# Rev_3.net
KiCad netlist of a schematic drawn in EAGLE
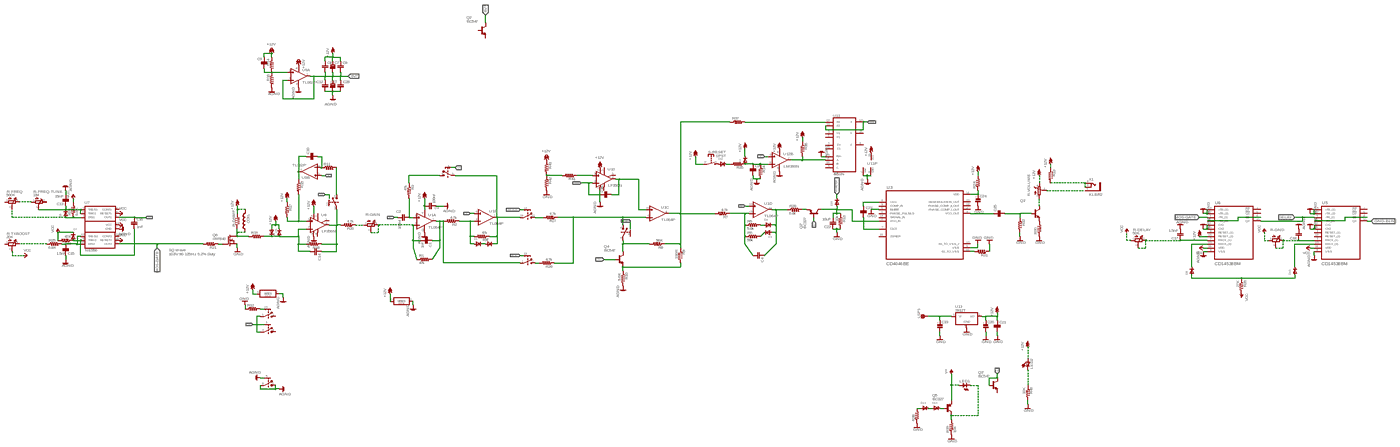
[diagram p0: schematic, sheet 1, overview]
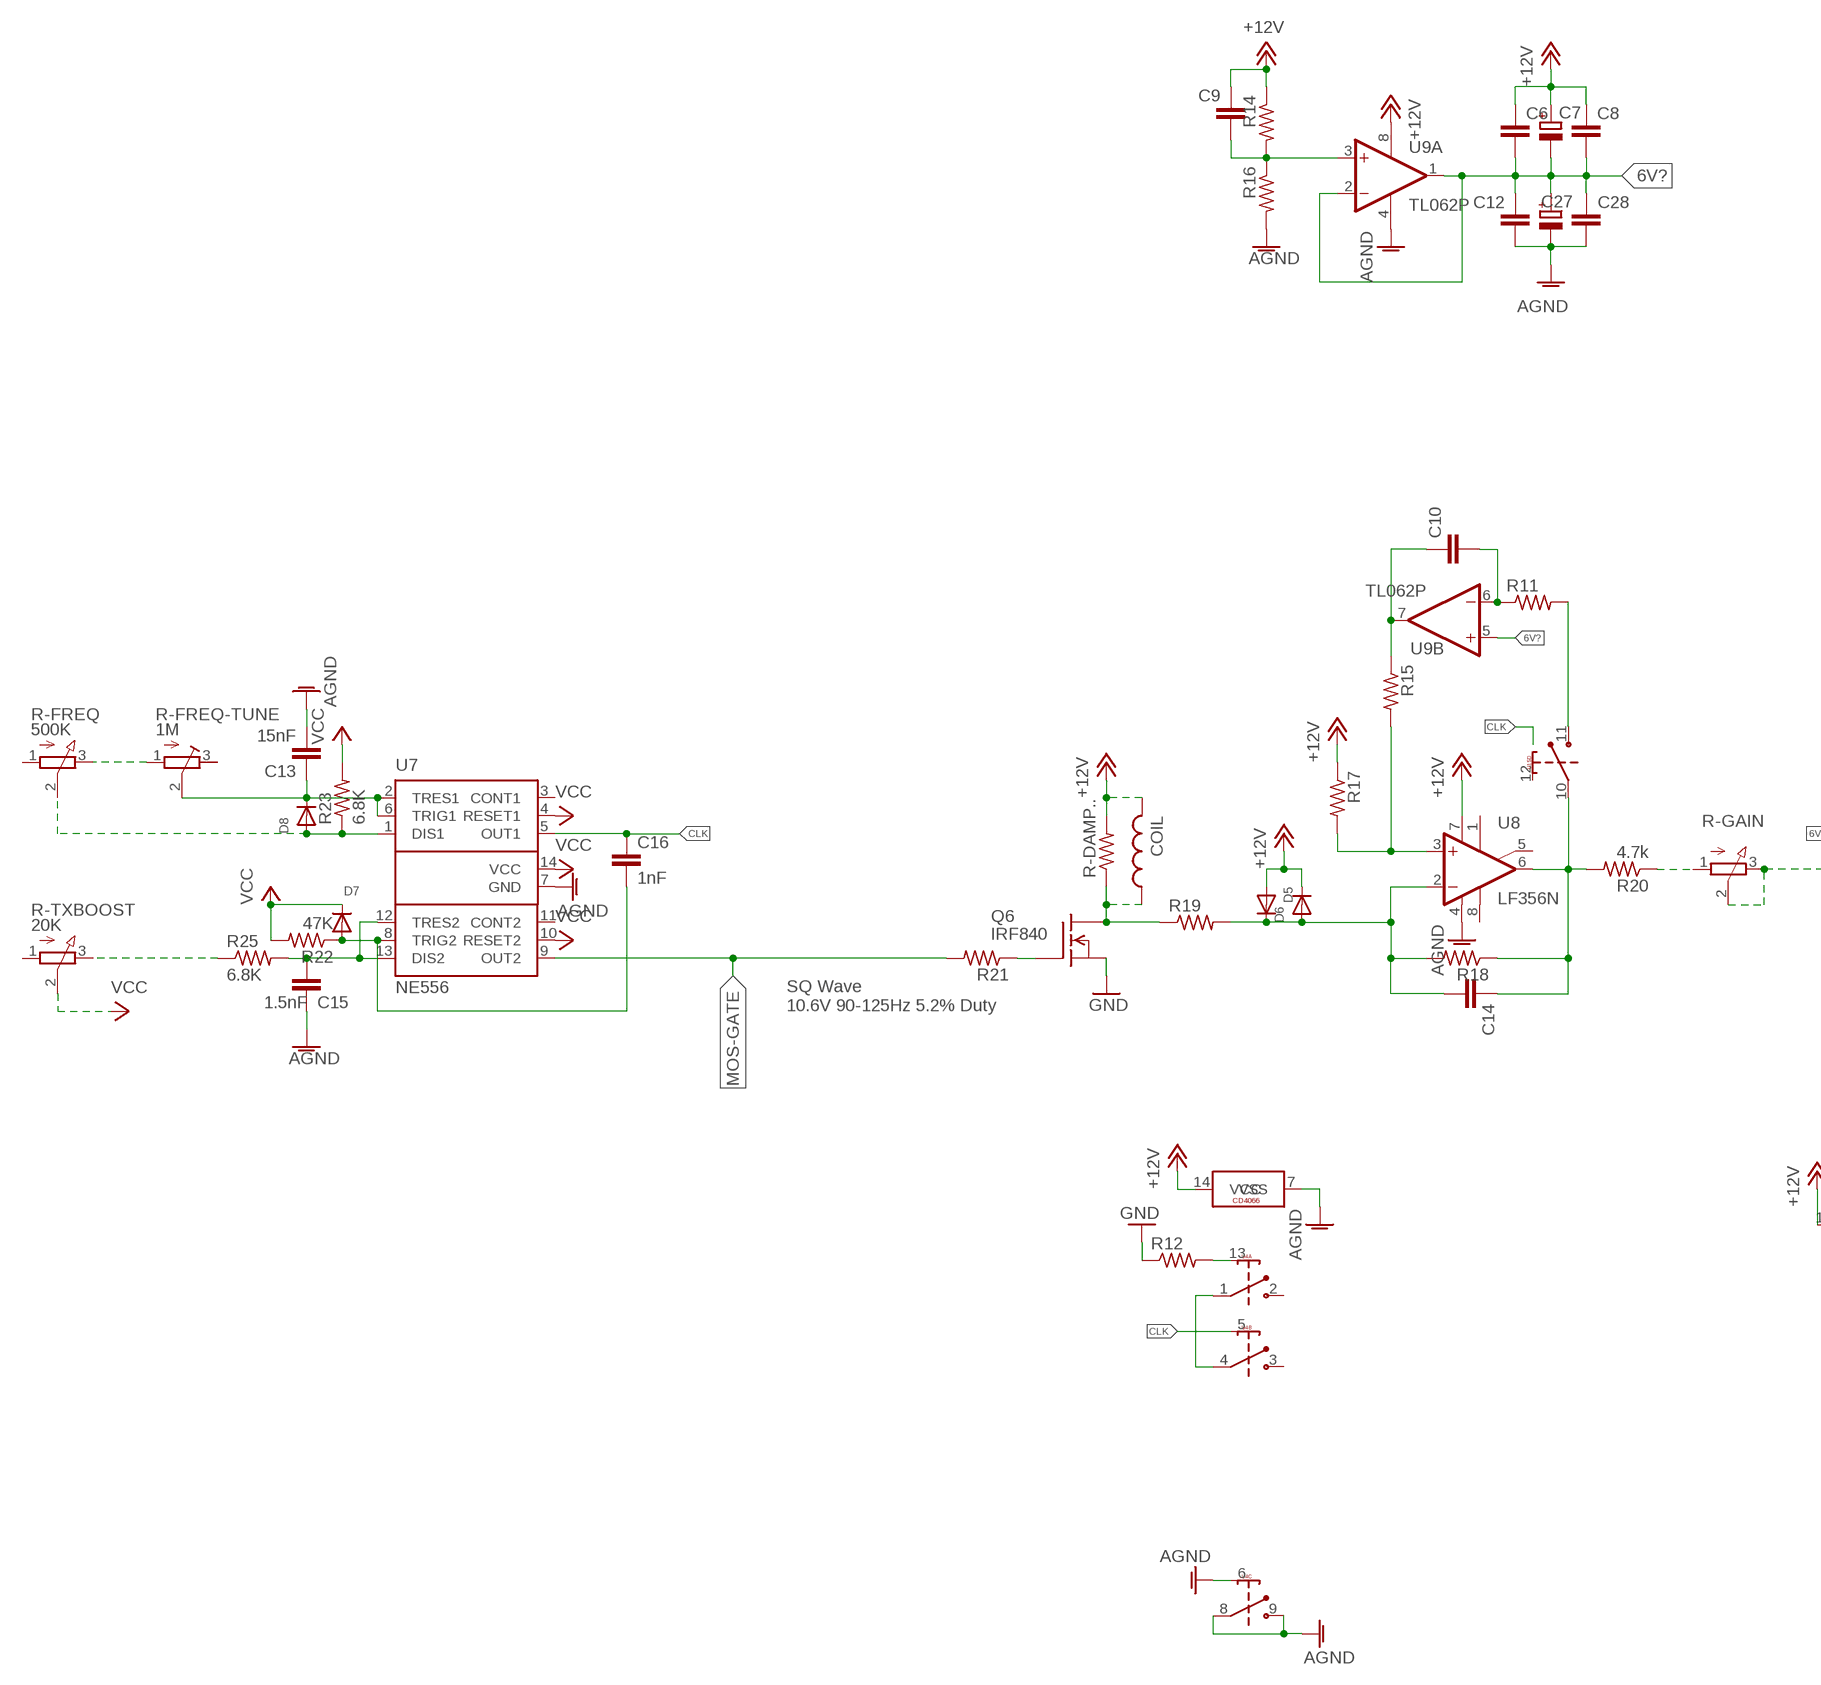
[diagram p1: schematic, sheet 1, part 1 of 4]
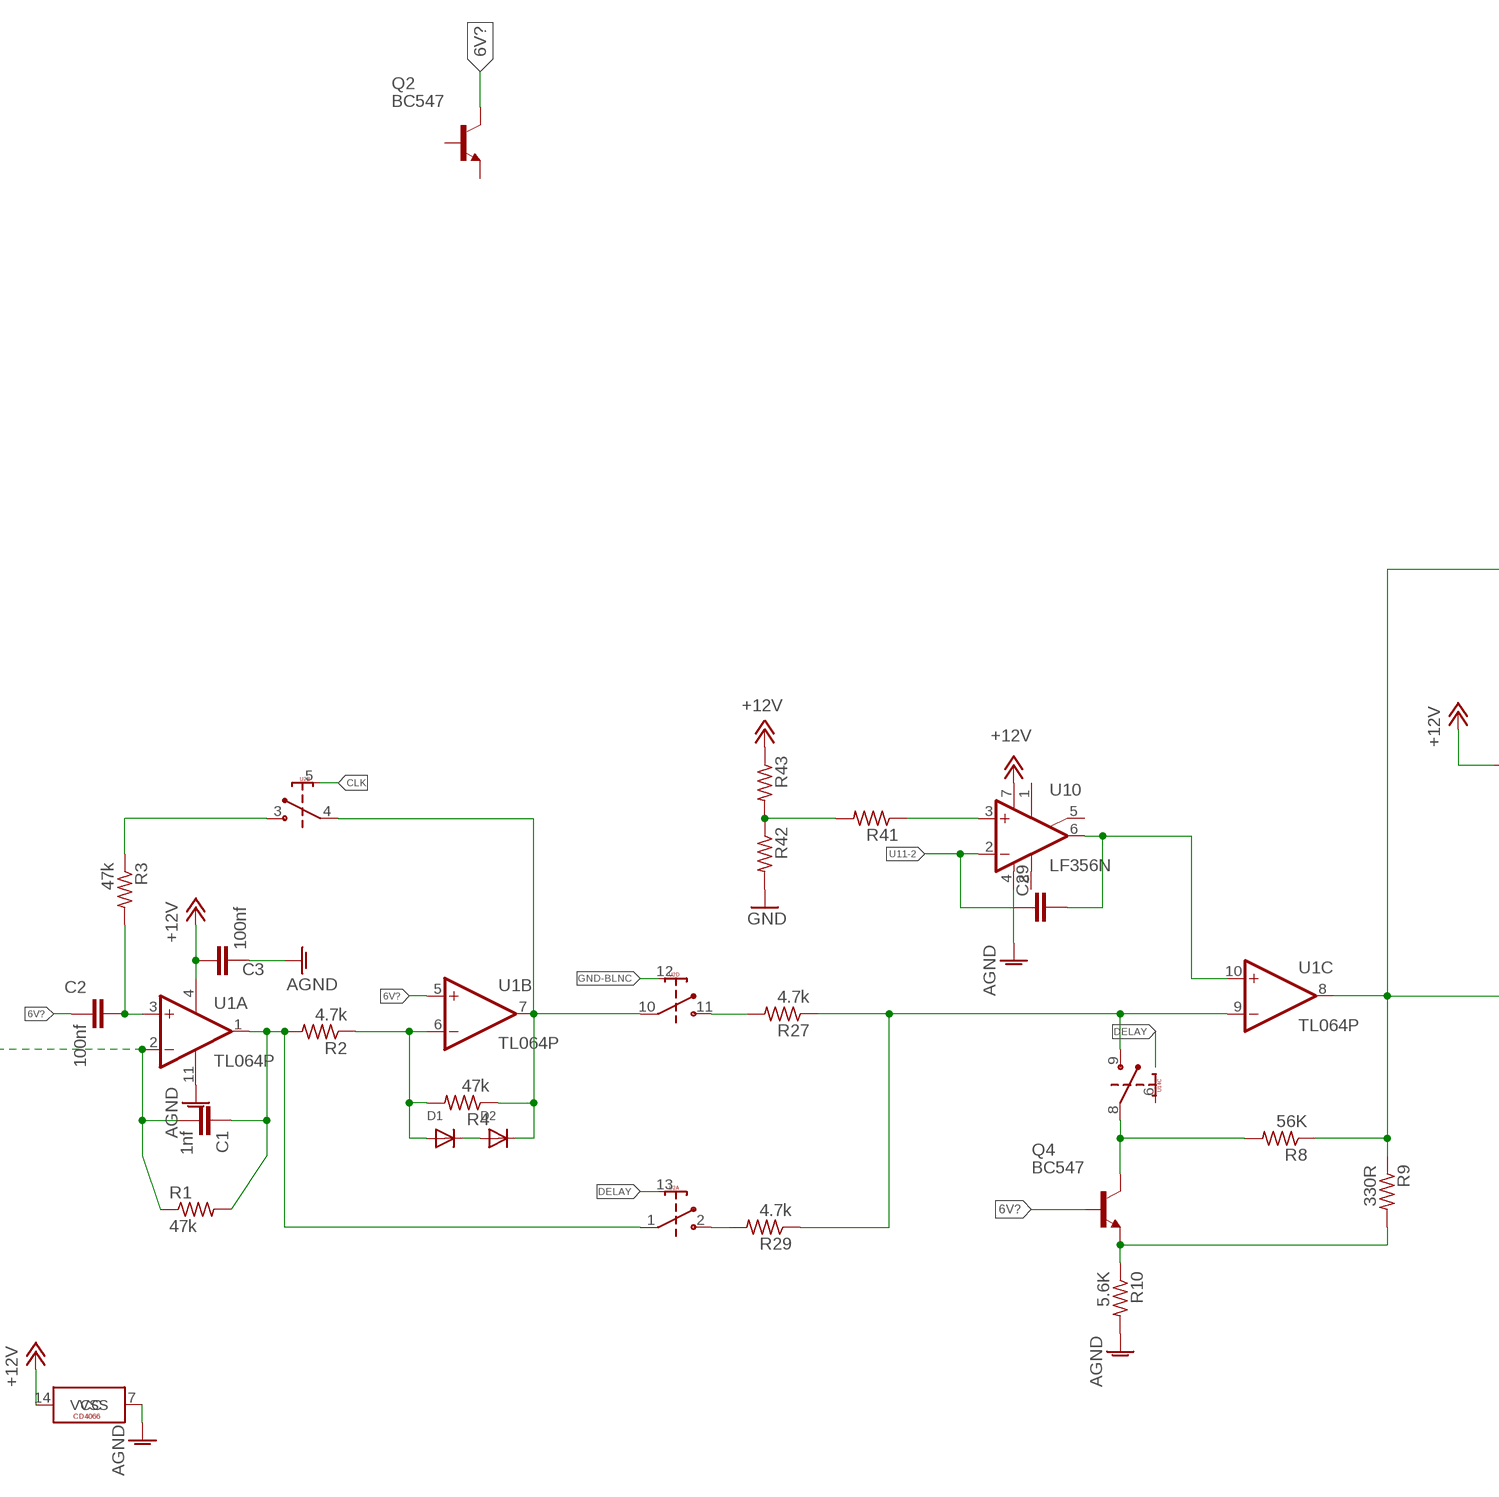
[diagram p2: schematic, sheet 1, part 2 of 4]
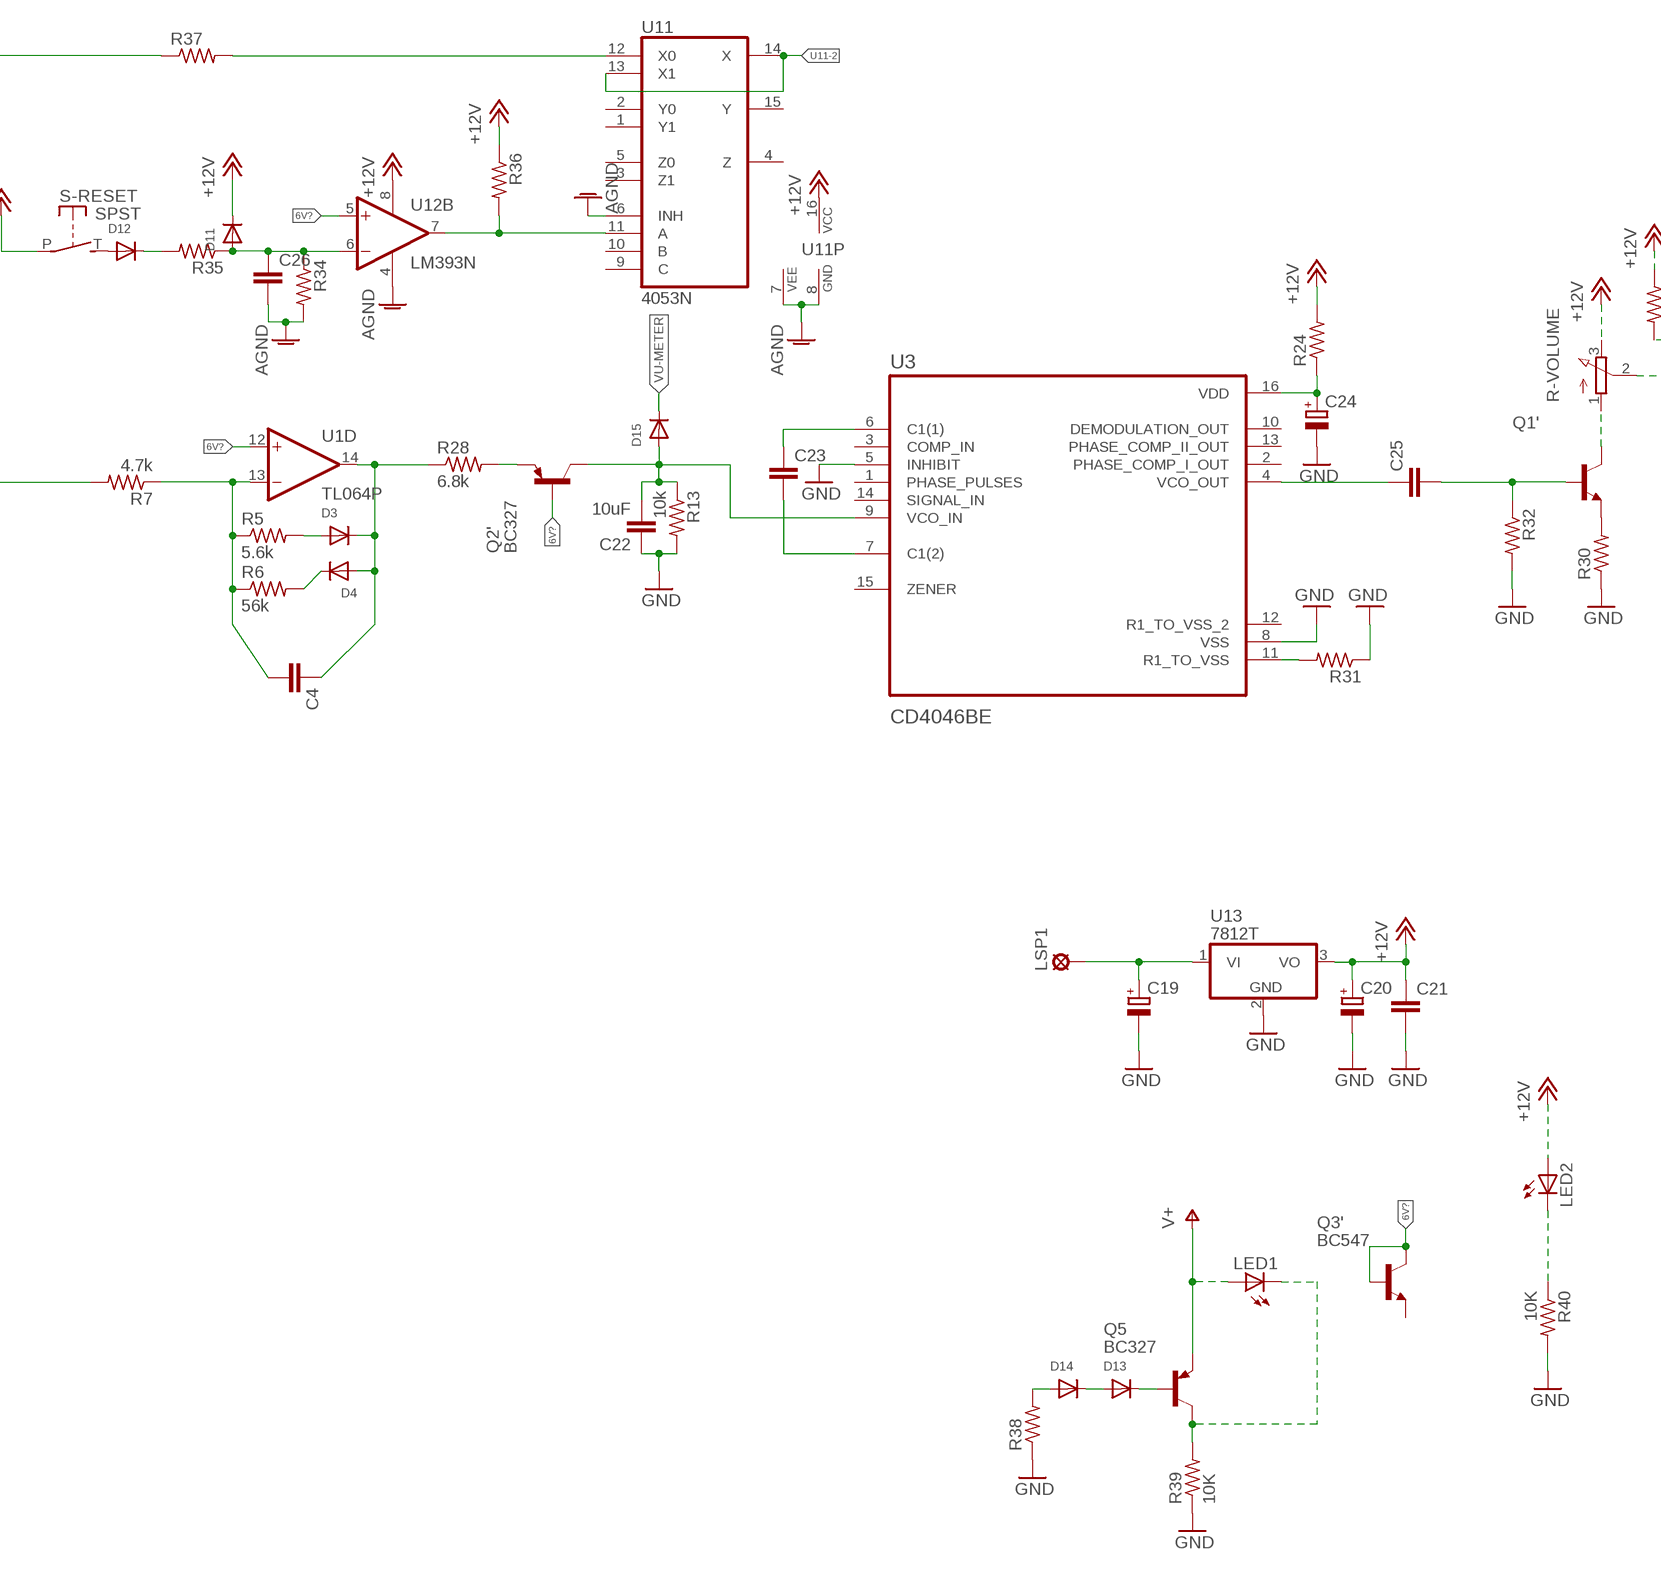
[diagram p3: schematic, sheet 1, part 3 of 4]
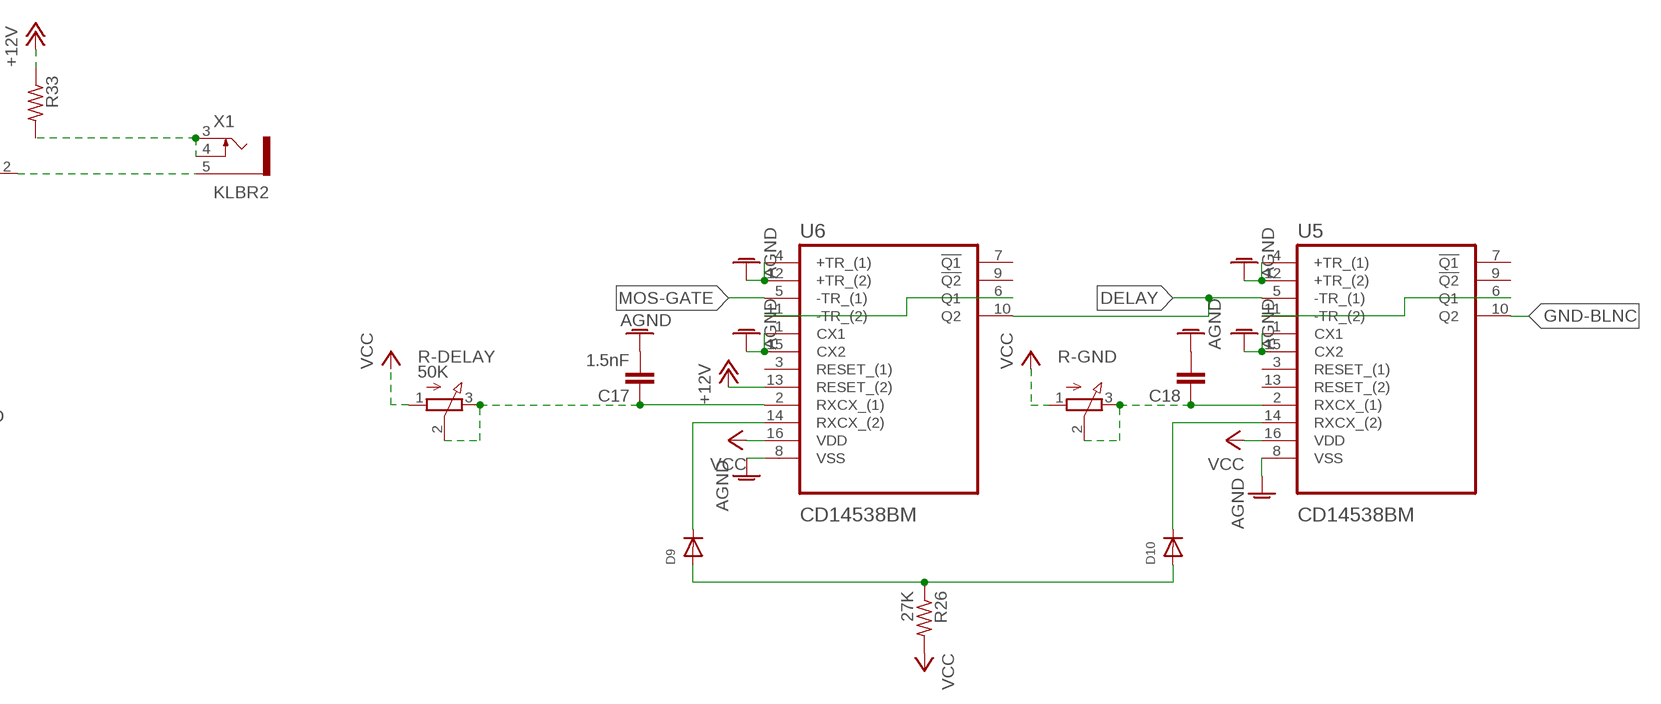
[diagram p4: schematic, sheet 1, part 4 of 4]

(export (version "E")
  (design (tool "Eeschema 10.0.6"))
  (components
    (comp (ref "C1")
      (value "1nf")
      (footprint "eagle-import:C050-025X075")
      (libsource (lib "eagle-import") (part "C-EU050-025X075"))
    )
    (comp (ref "C2")
      (value "100nf")
      (footprint "eagle-import:C050-025X075")
      (libsource (lib "eagle-import") (part "C-EU050-025X075"))
    )
    (comp (ref "C3")
      (value "100nf")
      (footprint "eagle-import:C050-025X075")
      (libsource (lib "eagle-import") (part "C-EU050-025X075"))
    )
    (comp (ref "C4")
      (value "C-EU050-025X075")
      (footprint "eagle-import:C050-025X075")
      (libsource (lib "eagle-import") (part "C-EU050-025X075"))
    )
    (comp (ref "C6")
      (value "C-EU050-025X075")
      (footprint "eagle-import:C050-025X075")
      (libsource (lib "eagle-import") (part "C-EU050-025X075"))
    )
    (comp (ref "C7")
      (value "CPOL-EU140CLH-0810")
      (footprint "eagle-import:140CLH-0810")
      (libsource (lib "eagle-import") (part "CPOL-EU140CLH-0810"))
    )
    (comp (ref "C8")
      (value "C-EU050-025X075")
      (footprint "eagle-import:C050-025X075")
      (libsource (lib "eagle-import") (part "C-EU050-025X075"))
    )
    (comp (ref "C9")
      (value "C-EU050-025X075")
      (footprint "eagle-import:C050-025X075")
      (libsource (lib "eagle-import") (part "C-EU050-025X075"))
    )
    (comp (ref "C10")
      (value "C-EU050-025X075")
      (footprint "eagle-import:C050-025X075")
      (libsource (lib "eagle-import") (part "C-EU050-025X075"))
    )
    (comp (ref "C12")
      (value "C-EU050-025X075")
      (footprint "eagle-import:C050-025X075")
      (libsource (lib "eagle-import") (part "C-EU050-025X075"))
    )
    (comp (ref "C13")
      (value "15nF")
      (footprint "eagle-import:C050-025X075")
      (libsource (lib "eagle-import") (part "C-EU050-025X075"))
    )
    (comp (ref "C14")
      (value "C-EU050-025X075")
      (footprint "eagle-import:C050-025X075")
      (libsource (lib "eagle-import") (part "C-EU050-025X075"))
    )
    (comp (ref "C15")
      (value "1.5nF")
      (footprint "eagle-import:C050-025X075")
      (libsource (lib "eagle-import") (part "C-EU050-025X075"))
    )
    (comp (ref "C16")
      (value "1nF")
      (footprint "eagle-import:C050-025X075")
      (libsource (lib "eagle-import") (part "C-EU050-025X075"))
    )
    (comp (ref "C17")
      (value "1.5nF")
      (footprint "eagle-import:C050-025X075")
      (libsource (lib "eagle-import") (part "C-EU050-025X075"))
    )
    (comp (ref "C18")
      (value "C-EU050-025X075")
      (footprint "eagle-import:C050-025X075")
      (libsource (lib "eagle-import") (part "C-EU050-025X075"))
    )
    (comp (ref "C19")
      (value "CPOL-EU140CLH-0810")
      (footprint "eagle-import:140CLH-0810")
      (libsource (lib "eagle-import") (part "CPOL-EU140CLH-0810"))
    )
    (comp (ref "C20")
      (value "CPOL-EU140CLH-0810")
      (footprint "eagle-import:140CLH-0810")
      (libsource (lib "eagle-import") (part "CPOL-EU140CLH-0810"))
    )
    (comp (ref "C21")
      (value "C-EU050-025X075")
      (footprint "eagle-import:C050-025X075")
      (libsource (lib "eagle-import") (part "C-EU050-025X075"))
    )
    (comp (ref "C22")
      (value "10uF")
      (footprint "eagle-import:C050-025X075")
      (libsource (lib "eagle-import") (part "C-EU050-025X075"))
    )
    (comp (ref "C23")
      (value "C-EU050-025X075")
      (footprint "eagle-import:C050-025X075")
      (libsource (lib "eagle-import") (part "C-EU050-025X075"))
    )
    (comp (ref "C24")
      (value "CPOL-EU140CLH-0810")
      (footprint "eagle-import:140CLH-0810")
      (libsource (lib "eagle-import") (part "CPOL-EU140CLH-0810"))
    )
    (comp (ref "C25")
      (value "C-EU050-025X075")
      (footprint "eagle-import:C050-025X075")
      (libsource (lib "eagle-import") (part "C-EU050-025X075"))
    )
    (comp (ref "C26")
      (value "C-EU050-025X075")
      (footprint "eagle-import:C050-025X075")
      (libsource (lib "eagle-import") (part "C-EU050-025X075"))
    )
    (comp (ref "C27")
      (value "CPOL-EU140CLH-0810")
      (footprint "eagle-import:140CLH-0810")
      (libsource (lib "eagle-import") (part "CPOL-EU140CLH-0810"))
    )
    (comp (ref "C28")
      (value "C-EU050-025X075")
      (footprint "eagle-import:C050-025X075")
      (libsource (lib "eagle-import") (part "C-EU050-025X075"))
    )
    (comp (ref "C29")
      (value "C-EU050-025X075")
      (footprint "eagle-import:C050-025X075")
      (libsource (lib "eagle-import") (part "C-EU050-025X075"))
    )
    (comp (ref "COIL")
      (value "L-USTJ4-U2")
      (footprint "eagle-import:TJ4-U2")
      (libsource (lib "eagle-import") (part "L-USTJ4-U2"))
    )
    (comp (ref "D1")
      (value "DIODEDO-1N4148")
      (footprint "eagle-import:DO-1N4148")
      (libsource (lib "eagle-import") (part "DIODEDO-1N4148"))
    )
    (comp (ref "D2")
      (value "DIODEDO-1N4148")
      (footprint "eagle-import:DO-1N4148")
      (libsource (lib "eagle-import") (part "DIODEDO-1N4148"))
    )
    (comp (ref "D3")
      (value "DIODEDO-1N4148")
      (footprint "eagle-import:DO-1N4148")
      (libsource (lib "eagle-import") (part "DIODEDO-1N4148"))
    )
    (comp (ref "D4")
      (value "DIODEDO-1N4148")
      (footprint "eagle-import:DO-1N4148")
      (libsource (lib "eagle-import") (part "DIODEDO-1N4148"))
    )
    (comp (ref "D5")
      (value "DIODEDO-1N4148")
      (footprint "eagle-import:DO-1N4148")
      (libsource (lib "eagle-import") (part "DIODEDO-1N4148"))
    )
    (comp (ref "D6")
      (value "DIODEDO-1N4148")
      (footprint "eagle-import:DO-1N4148")
      (libsource (lib "eagle-import") (part "DIODEDO-1N4148"))
    )
    (comp (ref "D7")
      (value "DIODEDO-1N4148")
      (footprint "eagle-import:DO-1N4148")
      (libsource (lib "eagle-import") (part "DIODEDO-1N4148"))
    )
    (comp (ref "D8")
      (value "DIODEDO-1N4148")
      (footprint "eagle-import:DO-1N4148")
      (libsource (lib "eagle-import") (part "DIODEDO-1N4148"))
    )
    (comp (ref "D9")
      (value "DIODEDO-1N4148")
      (footprint "eagle-import:DO-1N4148")
      (libsource (lib "eagle-import") (part "DIODEDO-1N4148"))
    )
    (comp (ref "D10")
      (value "DIODEDO-1N4148")
      (footprint "eagle-import:DO-1N4148")
      (libsource (lib "eagle-import") (part "DIODEDO-1N4148"))
    )
    (comp (ref "D11")
      (value "DIODEDO-1N4148")
      (footprint "eagle-import:DO-1N4148")
      (libsource (lib "eagle-import") (part "DIODEDO-1N4148"))
    )
    (comp (ref "D12")
      (value "DIODEDO-1N4148")
      (footprint "eagle-import:DO-1N4148")
      (libsource (lib "eagle-import") (part "DIODEDO-1N4148"))
    )
    (comp (ref "D13")
      (value "DIODEDO-1N4148")
      (footprint "eagle-import:DO-1N4148")
      (libsource (lib "eagle-import") (part "DIODEDO-1N4148"))
    )
    (comp (ref "D14")
      (value "DIODEDO-1N4148")
      (footprint "eagle-import:DO-1N4148")
      (libsource (lib "eagle-import") (part "DIODEDO-1N4148"))
    )
    (comp (ref "D15")
      (value "DIODEDO-1N4148")
      (footprint "eagle-import:DO-1N4148")
      (libsource (lib "eagle-import") (part "DIODEDO-1N4148"))
    )
    (comp (ref "LED1")
      (value "LED5MM")
      (footprint "eagle-import:LED5MM")
      (libsource (lib "eagle-import") (part "LED5MM"))
    )
    (comp (ref "LED2")
      (value "LED5MM")
      (footprint "eagle-import:LED5MM")
      (libsource (lib "eagle-import") (part "LED5MM"))
    )
    (comp (ref "LSP1")
      (value "SE14")
      (footprint "eagle-import:SE14")
      (libsource (lib "eagle-import") (part "SE14"))
    )
    (comp (ref "Q1'")
      (value "MPSA14-NPN-TO92-EBC")
      (footprint "eagle-import:TO92-EBC")
      (libsource (lib "eagle-import") (part "-NPN-TO92-EBCMPSA14"))
    )
    (comp (ref "Q2")
      (value "BC547")
      (footprint "eagle-import:TO92")
      (libsource (lib "eagle-import") (part "BC547"))
    )
    (comp (ref "Q2'")
      (value "BC327")
      (footprint "eagle-import:TO92")
      (libsource (lib "eagle-import") (part "BC327"))
    )
    (comp (ref "Q3'")
      (value "BC547")
      (footprint "eagle-import:TO92")
      (libsource (lib "eagle-import") (part "BC547"))
    )
    (comp (ref "Q4")
      (value "BC547")
      (footprint "eagle-import:TO92")
      (libsource (lib "eagle-import") (part "BC547"))
    )
    (comp (ref "Q5")
      (value "BC327")
      (footprint "eagle-import:TO92")
      (libsource (lib "eagle-import") (part "BC327"))
    )
    (comp (ref "Q6")
      (value "IRF840")
      (footprint "eagle-import:TO220")
      (libsource (lib "eagle-import") (part "IRF840"))
    )
    (comp (ref "R-DAMP..")
      (value "R-US_0207/7")
      (footprint "eagle-import:0207_7")
      (libsource (lib "eagle-import") (part "R-US_0207/7"))
    )
    (comp (ref "R-DELAY")
      (value "50K")
      (footprint "eagle-import:3RP_1610N")
      (libsource (lib "eagle-import") (part "3RP/1610N"))
    )
    (comp (ref "R-FREQ")
      (value "500K")
      (footprint "eagle-import:3RP_1610N")
      (libsource (lib "eagle-import") (part "3RP/1610N"))
    )
    (comp (ref "R-FREQ-TUNE")
      (value "1M")
      (footprint "eagle-import:RTRIM3296W")
      (libsource (lib "eagle-import") (part "R-TRIMM3296W"))
    )
    (comp (ref "R-GAIN")
      (value "3RP/1610N")
      (footprint "eagle-import:3RP_1610N")
      (libsource (lib "eagle-import") (part "3RP/1610N"))
    )
    (comp (ref "R-GND")
      (value "3RP/1610N")
      (footprint "eagle-import:3RP_1610N")
      (libsource (lib "eagle-import") (part "3RP/1610N"))
    )
    (comp (ref "R-TXBOOST")
      (value "20K")
      (footprint "eagle-import:3RP_1610N")
      (libsource (lib "eagle-import") (part "3RP/1610N"))
    )
    (comp (ref "R-VOLUME")
      (value "3RP/1610N")
      (footprint "eagle-import:3RP_1610N")
      (libsource (lib "eagle-import") (part "3RP/1610N"))
    )
    (comp (ref "R1")
      (value "47k")
      (footprint "eagle-import:0207_7")
      (libsource (lib "eagle-import") (part "R-US_0207/7"))
    )
    (comp (ref "R2")
      (value "4.7k")
      (footprint "eagle-import:0207_7")
      (libsource (lib "eagle-import") (part "R-US_0207/7"))
    )
    (comp (ref "R3")
      (value "47k")
      (footprint "eagle-import:0207_7")
      (libsource (lib "eagle-import") (part "R-US_0207/7"))
    )
    (comp (ref "R4")
      (value "47k")
      (footprint "eagle-import:0207_7")
      (libsource (lib "eagle-import") (part "R-US_0207/7"))
    )
    (comp (ref "R5")
      (value "5.6k")
      (footprint "eagle-import:0207_7")
      (libsource (lib "eagle-import") (part "R-US_0207/7"))
    )
    (comp (ref "R6")
      (value "56k")
      (footprint "eagle-import:0207_7")
      (libsource (lib "eagle-import") (part "R-US_0207/7"))
    )
    (comp (ref "R7")
      (value "4.7k")
      (footprint "eagle-import:0207_7")
      (libsource (lib "eagle-import") (part "R-US_0207/7"))
    )
    (comp (ref "R8")
      (value "56K")
      (footprint "eagle-import:0207_7")
      (libsource (lib "eagle-import") (part "R-US_0207/7"))
    )
    (comp (ref "R9")
      (value "330R")
      (footprint "eagle-import:0207_7")
      (libsource (lib "eagle-import") (part "R-US_0207/7"))
    )
    (comp (ref "R10")
      (value "5.6K")
      (footprint "eagle-import:0207_7")
      (libsource (lib "eagle-import") (part "R-US_0207/7"))
    )
    (comp (ref "R11")
      (value "R-US_0207/7")
      (footprint "eagle-import:0207_7")
      (libsource (lib "eagle-import") (part "R-US_0207/7"))
    )
    (comp (ref "R12")
      (value "R-US_0207/7")
      (footprint "eagle-import:0207_7")
      (libsource (lib "eagle-import") (part "R-US_0207/7"))
    )
    (comp (ref "R13")
      (value "10k")
      (footprint "eagle-import:0207_7")
      (libsource (lib "eagle-import") (part "R-US_0207/7"))
    )
    (comp (ref "R14")
      (value "R-US_0207/7")
      (footprint "eagle-import:0207_7")
      (libsource (lib "eagle-import") (part "R-US_0207/7"))
    )
    (comp (ref "R15")
      (value "R-US_0207/7")
      (footprint "eagle-import:0207_7")
      (libsource (lib "eagle-import") (part "R-US_0207/7"))
    )
    (comp (ref "R16")
      (value "R-US_0207/7")
      (footprint "eagle-import:0207_7")
      (libsource (lib "eagle-import") (part "R-US_0207/7"))
    )
    (comp (ref "R17")
      (value "R-US_0207/7")
      (footprint "eagle-import:0207_7")
      (libsource (lib "eagle-import") (part "R-US_0207/7"))
    )
    (comp (ref "R18")
      (value "R-US_0207/7")
      (footprint "eagle-import:0207_7")
      (libsource (lib "eagle-import") (part "R-US_0207/7"))
    )
    (comp (ref "R19")
      (value "R-US_0207/7")
      (footprint "eagle-import:0207_7")
      (libsource (lib "eagle-import") (part "R-US_0207/7"))
    )
    (comp (ref "R20")
      (value "4.7k")
      (footprint "eagle-import:0207_7")
      (libsource (lib "eagle-import") (part "R-US_0207/7"))
    )
    (comp (ref "R21")
      (value "R-US_0207/7")
      (footprint "eagle-import:0207_7")
      (libsource (lib "eagle-import") (part "R-US_0207/7"))
    )
    (comp (ref "R22")
      (value "47K")
      (footprint "eagle-import:0207_7")
      (libsource (lib "eagle-import") (part "R-US_0207/7"))
    )
    (comp (ref "R23")
      (value "6.8K")
      (footprint "eagle-import:0207_7")
      (libsource (lib "eagle-import") (part "R-US_0207/7"))
    )
    (comp (ref "R24")
      (value "R-US_0207/7")
      (footprint "eagle-import:0207_7")
      (libsource (lib "eagle-import") (part "R-US_0207/7"))
    )
    (comp (ref "R25")
      (value "6.8K")
      (footprint "eagle-import:0207_7")
      (libsource (lib "eagle-import") (part "R-US_0207/7"))
    )
    (comp (ref "R26")
      (value "27K")
      (footprint "eagle-import:0207_7")
      (libsource (lib "eagle-import") (part "R-US_0207/7"))
    )
    (comp (ref "R27")
      (value "4.7k")
      (footprint "eagle-import:0207_7")
      (libsource (lib "eagle-import") (part "R-US_0207/7"))
    )
    (comp (ref "R28")
      (value "6.8k")
      (footprint "eagle-import:0207_7")
      (libsource (lib "eagle-import") (part "R-US_0207/7"))
    )
    (comp (ref "R29")
      (value "4.7k")
      (footprint "eagle-import:0207_7")
      (libsource (lib "eagle-import") (part "R-US_0207/7"))
    )
    (comp (ref "R30")
      (value "R-US_0207/7")
      (footprint "eagle-import:0207_7")
      (libsource (lib "eagle-import") (part "R-US_0207/7"))
    )
    (comp (ref "R31")
      (value "R-US_0207/7")
      (footprint "eagle-import:0207_7")
      (libsource (lib "eagle-import") (part "R-US_0207/7"))
    )
    (comp (ref "R32")
      (value "R-US_0207/7")
      (footprint "eagle-import:0207_7")
      (libsource (lib "eagle-import") (part "R-US_0207/7"))
    )
    (comp (ref "R33")
      (value "R-US_0207/7")
      (footprint "eagle-import:0207_7")
      (libsource (lib "eagle-import") (part "R-US_0207/7"))
    )
    (comp (ref "R34")
      (value "R-US_0207/7")
      (footprint "eagle-import:0207_7")
      (libsource (lib "eagle-import") (part "R-US_0207/7"))
    )
    (comp (ref "R35")
      (value "R-US_0207/7")
      (footprint "eagle-import:0207_7")
      (libsource (lib "eagle-import") (part "R-US_0207/7"))
    )
    (comp (ref "R36")
      (value "R-US_0207/7")
      (footprint "eagle-import:0207_7")
      (libsource (lib "eagle-import") (part "R-US_0207/7"))
    )
    (comp (ref "R37")
      (value "R-US_0207/7")
      (footprint "eagle-import:0207_7")
      (libsource (lib "eagle-import") (part "R-US_0207/7"))
    )
    (comp (ref "R38")
      (value "R-US_0207/7")
      (footprint "eagle-import:0207_7")
      (libsource (lib "eagle-import") (part "R-US_0207/7"))
    )
    (comp (ref "R39")
      (value "10K")
      (footprint "eagle-import:0207_7")
      (libsource (lib "eagle-import") (part "R-US_0207/7"))
    )
    (comp (ref "R40")
      (value "10K")
      (footprint "eagle-import:0207_7")
      (libsource (lib "eagle-import") (part "R-US_0207/7"))
    )
    (comp (ref "R41")
      (value "R-US_0207/7")
      (footprint "eagle-import:0207_7")
      (libsource (lib "eagle-import") (part "R-US_0207/7"))
    )
    (comp (ref "R42")
      (value "R-US_0207/7")
      (footprint "eagle-import:0207_7")
      (libsource (lib "eagle-import") (part "R-US_0207/7"))
    )
    (comp (ref "R43")
      (value "R-US_0207/7")
      (footprint "eagle-import:0207_7")
      (libsource (lib "eagle-import") (part "R-US_0207/7"))
    )
    (comp (ref "S-RESET")
      (value "SPST")
      (footprint "eagle-import:JUDCOSPST")
      (libsource (lib "eagle-import") (part "SPST"))
    )
    (comp (ref "U1")
      (value "TL064P")
      (footprint "eagle-import:DIL14")
      (libsource (lib "eagle-import") (part "TL064P"))
    )
    (comp (ref "U2")
      (value "CD4066B")
      (footprint "eagle-import:DIP254P762X508-14")
      (libsource (lib "eagle-import") (part "CD4066B"))
    )
    (comp (ref "U3")
      (value "CD4046BE")
      (footprint "eagle-import:DIP794W45P254L1969H508Q16")
      (fields (field (name "MF") "Texas Instruments"))
      (libsource (lib "eagle-import") (part "CD4046BE"))
    )
    (comp (ref "U4")
      (value "CD4066B")
      (footprint "eagle-import:DIP254P762X508-14")
      (libsource (lib "eagle-import") (part "CD4066B"))
    )
    (comp (ref "U5")
      (value "CD14538BM")
      (footprint "eagle-import:SOIC127P600X175-16N")
      (fields (field (name "MF") "Texas Instruments"))
      (libsource (lib "eagle-import") (part "CD14538BM"))
    )
    (comp (ref "U6")
      (value "CD14538BM")
      (footprint "eagle-import:SOIC127P600X175-16N")
      (fields (field (name "MF") "Texas Instruments"))
      (libsource (lib "eagle-import") (part "CD14538BM"))
    )
    (comp (ref "U7")
      (value "NE556")
      (footprint "eagle-import:DIL14")
      (libsource (lib "eagle-import") (part "NE556"))
    )
    (comp (ref "U8")
      (value "LF356N")
      (footprint "eagle-import:DIL08")
      (libsource (lib "eagle-import") (part "LF356N"))
    )
    (comp (ref "U9")
      (value "TL062P")
      (footprint "eagle-import:DIL08")
      (libsource (lib "eagle-import") (part "TL062P"))
    )
    (comp (ref "U10")
      (value "LF356N")
      (footprint "eagle-import:DIL08")
      (libsource (lib "eagle-import") (part "LF356N"))
    )
    (comp (ref "U11")
      (value "4053N")
      (footprint "eagle-import:DIL16")
      (libsource (lib "eagle-import") (part "4053N"))
    )
    (comp (ref "U12")
      (value "LM393N")
      (footprint "eagle-import:DIL08")
      (libsource (lib "eagle-import") (part "LM393N"))
    )
    (comp (ref "U13")
      (value "7812T")
      (footprint "eagle-import:TO220H")
      (libsource (lib "eagle-import") (part "78T12"))
    )
    (comp (ref "U14")
      (value "CD4066B")
      (footprint "eagle-import:DIP254P762X508-14")
      (libsource (lib "eagle-import") (part "CD4066B"))
    )
    (comp (ref "U15")
      (value "CD4066B")
      (footprint "eagle-import:DIP254P762X508-14")
      (libsource (lib "eagle-import") (part "CD4066B"))
    )
    (comp (ref "X1")
      (value "KLBR2")
      (footprint "eagle-import:KLBR2")
      (libsource (lib "eagle-import") (part "KLBR?2"))
    )
  )
  (nets
    (net (code "1") (name "+12V") (class "Default")
      (node (ref "C20") (pin "+") (pinfunction "+_+") (pintype "passive"))
      (node (ref "C21") (pin "1") (pinfunction "1_1") (pintype "passive"))
      (node (ref "C3") (pin "1") (pinfunction "1_1") (pintype "passive"))
      (node (ref "C6") (pin "1") (pinfunction "1_1") (pintype "passive"))
      (node (ref "C7") (pin "+") (pinfunction "+_+") (pintype "passive"))
      (node (ref "C8") (pin "1") (pinfunction "1_1") (pintype "passive"))
      (node (ref "C9") (pin "1") (pinfunction "1_1") (pintype "passive"))
      (node (ref "COIL") (pin "2") (pinfunction "2_2") (pintype "passive"))
      (node (ref "D11") (pin "C") (pinfunction "C_C") (pintype "passive"))
      (node (ref "D5") (pin "A") (pinfunction "A_A") (pintype "passive"))
      (node (ref "D6") (pin "C") (pinfunction "C_C") (pintype "passive"))
      (node (ref "LED2") (pin "A") (pinfunction "A_A") (pintype "passive"))
      (node (ref "R-DAMP..") (pin "2") (pinfunction "2_2") (pintype "passive"))
      (node (ref "R-VOLUME") (pin "3") (pinfunction "E_3") (pintype "passive"))
      (node (ref "R14") (pin "1") (pinfunction "1_1") (pintype "passive"))
      (node (ref "R17") (pin "1") (pinfunction "1_1") (pintype "passive"))
      (node (ref "R24") (pin "2") (pinfunction "2_2") (pintype "passive"))
      (node (ref "R33") (pin "1") (pinfunction "1_1") (pintype "passive"))
      (node (ref "R36") (pin "1") (pinfunction "1_1") (pintype "passive"))
      (node (ref "R43") (pin "1") (pinfunction "1_1") (pintype "passive"))
      (node (ref "S-RESET") (pin "P") (pinfunction "P_P") (pintype "passive"))
      (node (ref "U1") (pin "4") (pinfunction "V+_4") (pintype "power_in"))
      (node (ref "U10") (pin "7") (pinfunction "V+_7") (pintype "power_in"))
      (node (ref "U11") (pin "16") (pinfunction "VCC_16") (pintype "power_in"))
      (node (ref "U12") (pin "8") (pinfunction "V+_8") (pintype "power_in"))
      (node (ref "U13") (pin "3") (pinfunction "VO_3") (pintype "passive"))
      (node (ref "U2") (pin "14") (pinfunction "VCC_14") (pintype "bidirectional"))
      (node (ref "U4") (pin "14") (pinfunction "VCC_14") (pintype "bidirectional"))
      (node (ref "U6") (pin "13") (pinfunction "RESET_(2)_13") (pintype "input"))
      (node (ref "U8") (pin "7") (pinfunction "V+_7") (pintype "power_in"))
      (node (ref "U9") (pin "8") (pinfunction "V+_8") (pintype "power_in"))
    )
    (net (code "2") (name "/R1_TO_VSS_2") (class "Default")
      (node (ref "U3") (pin "12") (pinfunction "R1_TO_VSS_2_12") (pintype "power_in"))
    )
    (net (code "3") (name "6V?") (class "Default")
      (node (ref "C12") (pin "1") (pinfunction "1_1") (pintype "passive"))
      (node (ref "C2") (pin "2") (pinfunction "2_2") (pintype "passive"))
      (node (ref "C27") (pin "+") (pinfunction "+_+") (pintype "passive"))
      (node (ref "C28") (pin "1") (pinfunction "1_1") (pintype "passive"))
      (node (ref "C6") (pin "2") (pinfunction "2_2") (pintype "passive"))
      (node (ref "C7") (pin "-") (pinfunction "-_-") (pintype "passive"))
      (node (ref "C8") (pin "2") (pinfunction "2_2") (pintype "passive"))
      (node (ref "Q2") (pin "3") (pinfunction "C_3") (pintype "passive"))
      (node (ref "Q2'") (pin "2") (pinfunction "B_2") (pintype "passive"))
      (node (ref "Q3'") (pin "2") (pinfunction "B_2") (pintype "passive"))
      (node (ref "Q3'") (pin "3") (pinfunction "C_3") (pintype "passive"))
      (node (ref "Q4") (pin "2") (pinfunction "B_2") (pintype "passive"))
      (node (ref "U1") (pin "12") (pinfunction "+IN_12") (pintype "input"))
      (node (ref "U1") (pin "5") (pinfunction "+IN_5") (pintype "input"))
      (node (ref "U12") (pin "5") (pinfunction "+IN_5") (pintype "input"))
      (node (ref "U9") (pin "1") (pinfunction "OUT_1") (pintype "output"))
      (node (ref "U9") (pin "2") (pinfunction "-IN_2") (pintype "input"))
      (node (ref "U9") (pin "5") (pinfunction "+IN_5") (pintype "input"))
    )
    (net (code "4") (name "AGND") (class "Default")
      (node (ref "C12") (pin "2") (pinfunction "2_2") (pintype "passive"))
      (node (ref "C13") (pin "2") (pinfunction "2_2") (pintype "passive"))
      (node (ref "C15") (pin "2") (pinfunction "2_2") (pintype "passive"))
      (node (ref "C17") (pin "2") (pinfunction "2_2") (pintype "passive"))
      (node (ref "C18") (pin "2") (pinfunction "2_2") (pintype "passive"))
      (node (ref "C26") (pin "2") (pinfunction "2_2") (pintype "passive"))
      (node (ref "C27") (pin "-") (pinfunction "-_-") (pintype "passive"))
      (node (ref "C28") (pin "2") (pinfunction "2_2") (pintype "passive"))
      (node (ref "C3") (pin "2") (pinfunction "2_2") (pintype "passive"))
      (node (ref "R10") (pin "2") (pinfunction "2_2") (pintype "passive"))
      (node (ref "R16") (pin "2") (pinfunction "2_2") (pintype "passive"))
      (node (ref "R34") (pin "2") (pinfunction "2_2") (pintype "passive"))
      (node (ref "U1") (pin "11") (pinfunction "V-_11") (pintype "power_in"))
      (node (ref "U10") (pin "4") (pinfunction "V-_4") (pintype "power_in"))
      (node (ref "U11") (pin "6") (pinfunction "INH_6") (pintype "input"))
      (node (ref "U11") (pin "7") (pinfunction "VEE_7") (pintype "power_in"))
      (node (ref "U11") (pin "8") (pinfunction "GND_8") (pintype "power_in"))
      (node (ref "U12") (pin "4") (pinfunction "V-_4") (pintype "power_in"))
      (node (ref "U2") (pin "7") (pinfunction "VSS_7") (pintype "bidirectional"))
      (node (ref "U4") (pin "6") (pinfunction "CTRL_6") (pintype "bidirectional"))
      (node (ref "U4") (pin "7") (pinfunction "VSS_7") (pintype "bidirectional"))
      (node (ref "U4") (pin "8") (pinfunction "IN_8") (pintype "bidirectional"))
      (node (ref "U4") (pin "9") (pinfunction "OUT_9") (pintype "bidirectional"))
      (node (ref "U5") (pin "1") (pinfunction "CX1_1") (pintype "input"))
      (node (ref "U5") (pin "12") (pinfunction "+TR_(2)_12") (pintype "input"))
      (node (ref "U5") (pin "15") (pinfunction "CX2_15") (pintype "input"))
      (node (ref "U5") (pin "4") (pinfunction "+TR_(1)_4") (pintype "input"))
      (node (ref "U5") (pin "8") (pinfunction "VSS_8") (pintype "input"))
      (node (ref "U6") (pin "1") (pinfunction "CX1_1") (pintype "input"))
      (node (ref "U6") (pin "12") (pinfunction "+TR_(2)_12") (pintype "input"))
      (node (ref "U6") (pin "15") (pinfunction "CX2_15") (pintype "input"))
      (node (ref "U6") (pin "4") (pinfunction "+TR_(1)_4") (pintype "input"))
      (node (ref "U6") (pin "8") (pinfunction "VSS_8") (pintype "input"))
      (node (ref "U7") (pin "7") (pinfunction "GND_7") (pintype "power_in"))
      (node (ref "U8") (pin "4") (pinfunction "V-_4") (pintype "power_in"))
      (node (ref "U9") (pin "4") (pinfunction "V-_4") (pintype "power_in"))
    )
    (net (code "5") (name "CLK") (class "Default")
      (node (ref "C16") (pin "1") (pinfunction "1_1") (pintype "passive"))
      (node (ref "U2") (pin "5") (pinfunction "CTRL_5") (pintype "bidirectional"))
      (node (ref "U4") (pin "5") (pinfunction "CTRL_5") (pintype "bidirectional"))
      (node (ref "U7") (pin "5") (pinfunction "OUT1_5") (pintype "output"))
    )
    (net (code "6") (name "DELAY") (class "Default")
      (node (ref "U2") (pin "13") (pinfunction "CTRL_13") (pintype "bidirectional"))
      (node (ref "U5") (pin "5") (pinfunction "-TR_(1)_5") (pintype "input"))
      (node (ref "U6") (pin "10") (pinfunction "Q2_10") (pintype "output"))
    )
    (net (code "7") (name "GND") (class "Default")
      (node (ref "C19") (pin "-") (pinfunction "-_-") (pintype "passive"))
      (node (ref "C20") (pin "-") (pinfunction "-_-") (pintype "passive"))
      (node (ref "C21") (pin "2") (pinfunction "2_2") (pintype "passive"))
      (node (ref "C22") (pin "1") (pinfunction "1_1") (pintype "passive"))
      (node (ref "C24") (pin "-") (pinfunction "-_-") (pintype "passive"))
      (node (ref "Q6") (pin "3") (pinfunction "S_3") (pintype "passive"))
      (node (ref "R12") (pin "1") (pinfunction "1_1") (pintype "passive"))
      (node (ref "R13") (pin "2") (pinfunction "2_2") (pintype "passive"))
      (node (ref "R30") (pin "1") (pinfunction "1_1") (pintype "passive"))
      (node (ref "R31") (pin "1") (pinfunction "1_1") (pintype "passive"))
      (node (ref "R32") (pin "2") (pinfunction "2_2") (pintype "passive"))
      (node (ref "R38") (pin "1") (pinfunction "1_1") (pintype "passive"))
      (node (ref "R39") (pin "1") (pinfunction "1_1") (pintype "passive"))
      (node (ref "R40") (pin "2") (pinfunction "2_2") (pintype "passive"))
      (node (ref "R42") (pin "2") (pinfunction "2_2") (pintype "passive"))
      (node (ref "U13") (pin "2") (pinfunction "GND_2") (pintype "passive"))
      (node (ref "U3") (pin "5") (pinfunction "INHIBIT_5") (pintype "input"))
      (node (ref "U3") (pin "8") (pinfunction "VSS_8") (pintype "power_in"))
    )
    (net (code "8") (name "GND-BLNC") (class "Default")
      (node (ref "U2") (pin "12") (pinfunction "CTRL_12") (pintype "bidirectional"))
      (node (ref "U5") (pin "10") (pinfunction "Q2_10") (pintype "output"))
    )
    (net (code "9") (name "MOS-GATE") (class "Default")
      (node (ref "R21") (pin "2") (pinfunction "2_2") (pintype "passive"))
      (node (ref "U6") (pin "5") (pinfunction "-TR_(1)_5") (pintype "input"))
      (node (ref "U7") (pin "9") (pinfunction "OUT2_9") (pintype "output"))
    )
    (net (code "10") (name "Net-(C25-Pad2)") (class "Default")
      (node (ref "C25") (pin "2") (pinfunction "2_2") (pintype "passive"))
      (node (ref "Q1'") (pin "B") (pinfunction "B_B") (pintype "passive"))
      (node (ref "R32") (pin "1") (pinfunction "1_1") (pintype "passive"))
    )
    (net (code "11") (name "Net-(D1-PadC)") (class "Default")
      (node (ref "D1") (pin "C") (pinfunction "C_C") (pintype "passive"))
      (node (ref "D2") (pin "A") (pinfunction "A_A") (pintype "passive"))
    )
    (net (code "12") (name "Net-(D3-PadA)") (class "Default")
      (node (ref "D3") (pin "A") (pinfunction "A_A") (pintype "passive"))
      (node (ref "R5") (pin "2") (pinfunction "2_2") (pintype "passive"))
    )
    (net (code "13") (name "Net-(D4-PadC)") (class "Default")
      (node (ref "D4") (pin "C") (pinfunction "C_C") (pintype "passive"))
      (node (ref "R6") (pin "2") (pinfunction "2_2") (pintype "passive"))
    )
    (net (code "14") (name "Net-(D10-PadA)") (class "Default")
      (node (ref "D10") (pin "A") (pinfunction "A_A") (pintype "passive"))
      (node (ref "D9") (pin "A") (pinfunction "A_A") (pintype "passive"))
      (node (ref "R26") (pin "1") (pinfunction "1_1") (pintype "passive"))
    )
    (net (code "15") (name "Net-(D12-PadC)") (class "Default")
      (node (ref "D12") (pin "C") (pinfunction "C_C") (pintype "passive"))
      (node (ref "R35") (pin "2") (pinfunction "2_2") (pintype "passive"))
    )
    (net (code "16") (name "Net-(D13-PadA)") (class "Default")
      (node (ref "D13") (pin "A") (pinfunction "A_A") (pintype "passive"))
      (node (ref "D14") (pin "C") (pinfunction "C_C") (pintype "passive"))
    )
    (net (code "17") (name "Net-(D14-PadA)") (class "Default")
      (node (ref "D14") (pin "A") (pinfunction "A_A") (pintype "passive"))
      (node (ref "R38") (pin "2") (pinfunction "2_2") (pintype "passive"))
    )
    (net (code "18") (name "Net-(LED1-C)") (class "Default")
      (node (ref "LED1") (pin "K") (pinfunction "C_K") (pintype "passive"))
      (node (ref "Q5") (pin "3") (pinfunction "C_3") (pintype "passive"))
      (node (ref "R39") (pin "2") (pinfunction "2_2") (pintype "passive"))
    )
    (net (code "19") (name "Net-(LED2-C)") (class "Default")
      (node (ref "LED2") (pin "K") (pinfunction "C_K") (pintype "passive"))
      (node (ref "R40") (pin "1") (pinfunction "1_1") (pintype "passive"))
    )
    (net (code "20") (name "Net-(Q1'-PadE)") (class "Default")
      (node (ref "Q1'") (pin "E") (pinfunction "E_E") (pintype "passive"))
      (node (ref "R30") (pin "2") (pinfunction "2_2") (pintype "passive"))
    )
    (net (code "21") (name "Net-(Q2'-C)") (class "Default")
      (node (ref "C22") (pin "2") (pinfunction "2_2") (pintype "passive"))
      (node (ref "D15") (pin "A") (pinfunction "A_A") (pintype "passive"))
      (node (ref "Q2'") (pin "3") (pinfunction "C_3") (pintype "passive"))
      (node (ref "R13") (pin "1") (pinfunction "1_1") (pintype "passive"))
      (node (ref "U3") (pin "9") (pinfunction "VCO_IN_9") (pintype "input"))
    )
    (net (code "22") (name "Net-(Q2'-E)") (class "Default")
      (node (ref "Q2'") (pin "1") (pinfunction "E_1") (pintype "passive"))
      (node (ref "R28") (pin "2") (pinfunction "2_2") (pintype "passive"))
    )
    (net (code "23") (name "Net-(Q4-C)") (class "Default")
      (node (ref "Q4") (pin "3") (pinfunction "C_3") (pintype "passive"))
      (node (ref "R8") (pin "2") (pinfunction "2_2") (pintype "passive"))
      (node (ref "U14") (pin "8") (pinfunction "IN_8") (pintype "bidirectional"))
    )
    (net (code "24") (name "Net-(Q4-E)") (class "Default")
      (node (ref "Q4") (pin "1") (pinfunction "E_1") (pintype "passive"))
      (node (ref "R10") (pin "1") (pinfunction "1_1") (pintype "passive"))
      (node (ref "R9") (pin "2") (pinfunction "2_2") (pintype "passive"))
    )
    (net (code "25") (name "Net-(Q5-B)") (class "Default")
      (node (ref "D13") (pin "C") (pinfunction "C_C") (pintype "passive"))
      (node (ref "Q5") (pin "2") (pinfunction "B_2") (pintype "passive"))
    )
    (net (code "26") (name "Net-(Q6-D)") (class "Default")
      (node (ref "COIL") (pin "1") (pinfunction "1_1") (pintype "passive"))
      (node (ref "Q6") (pin "2") (pinfunction "D_2") (pintype "passive"))
      (node (ref "R-DAMP..") (pin "1") (pinfunction "1_1") (pintype "passive"))
      (node (ref "R19") (pin "1") (pinfunction "1_1") (pintype "passive"))
    )
    (net (code "27") (name "Net-(Q6-G)") (class "Default")
      (node (ref "Q6") (pin "1") (pinfunction "G_1") (pintype "passive"))
      (node (ref "R21") (pin "1") (pinfunction "1_1") (pintype "passive"))
    )
    (net (code "28") (name "Net-(R-DELAY-E)") (class "Default")
      (node (ref "C17") (pin "1") (pinfunction "1_1") (pintype "passive"))
      (node (ref "R-DELAY") (pin "2") (pinfunction "S_2") (pintype "passive"))
      (node (ref "R-DELAY") (pin "3") (pinfunction "E_3") (pintype "passive"))
      (node (ref "U6") (pin "2") (pinfunction "RXCX_(1)_2") (pintype "input"))
    )
    (net (code "29") (name "Net-(R-FREQ-E)") (class "Default")
      (node (ref "R-FREQ") (pin "3") (pinfunction "E_3") (pintype "passive"))
      (node (ref "R-FREQ-TUNE") (pin "1") (pinfunction "A_1") (pintype "passive"))
    )
    (net (code "30") (name "Net-(R-FREQ-S)") (class "Default")
      (node (ref "D8") (pin "A") (pinfunction "A_A") (pintype "passive"))
      (node (ref "R-FREQ") (pin "2") (pinfunction "S_2") (pintype "passive"))
      (node (ref "R23") (pin "1") (pinfunction "1_1") (pintype "passive"))
      (node (ref "U7") (pin "1") (pinfunction "DIS1_1") (pintype "input"))
    )
    (net (code "31") (name "Net-(R-FREQ-TUNE-S)") (class "Default")
      (node (ref "C13") (pin "1") (pinfunction "1_1") (pintype "passive"))
      (node (ref "D8") (pin "C") (pinfunction "C_C") (pintype "passive"))
      (node (ref "R-FREQ-TUNE") (pin "2") (pinfunction "S_2") (pintype "passive"))
      (node (ref "U7") (pin "2") (pinfunction "TRES1_2") (pintype "input"))
      (node (ref "U7") (pin "6") (pinfunction "TRIG1_6") (pintype "input"))
    )
    (net (code "32") (name "Net-(R-GAIN-A)") (class "Default")
      (node (ref "R-GAIN") (pin "1") (pinfunction "A_1") (pintype "passive"))
      (node (ref "R20") (pin "1") (pinfunction "1_1") (pintype "passive"))
    )
    (net (code "33") (name "Net-(R-GAIN-E)") (class "Default")
      (node (ref "C1") (pin "2") (pinfunction "2_2") (pintype "passive"))
      (node (ref "R-GAIN") (pin "2") (pinfunction "S_2") (pintype "passive"))
      (node (ref "R-GAIN") (pin "3") (pinfunction "E_3") (pintype "passive"))
      (node (ref "R1") (pin "1") (pinfunction "1_1") (pintype "passive"))
      (node (ref "U1") (pin "2") (pinfunction "-IN_2") (pintype "input"))
    )
    (net (code "34") (name "Net-(R-GND-E)") (class "Default")
      (node (ref "C18") (pin "1") (pinfunction "1_1") (pintype "passive"))
      (node (ref "R-GND") (pin "2") (pinfunction "S_2") (pintype "passive"))
      (node (ref "R-GND") (pin "3") (pinfunction "E_3") (pintype "passive"))
      (node (ref "U5") (pin "2") (pinfunction "RXCX_(1)_2") (pintype "input"))
    )
    (net (code "35") (name "Net-(R-TXBOOST-E)") (class "Default")
      (node (ref "R-TXBOOST") (pin "3") (pinfunction "E_3") (pintype "passive"))
      (node (ref "R25") (pin "1") (pinfunction "1_1") (pintype "passive"))
    )
    (net (code "36") (name "Net-(R-VOLUME-A)") (class "Default")
      (node (ref "Q1'") (pin "C") (pinfunction "C_C") (pintype "passive"))
      (node (ref "R-VOLUME") (pin "1") (pinfunction "A_1") (pintype "passive"))
    )
    (net (code "37") (name "Net-(R-VOLUME-S)") (class "Default")
      (node (ref "R-VOLUME") (pin "2") (pinfunction "S_2") (pintype "passive"))
      (node (ref "X1") (pin "5") (pinfunction "5_5") (pintype "passive"))
    )
    (net (code "38") (name "Net-(R33-Pad2)") (class "Default")
      (node (ref "R33") (pin "2") (pinfunction "2_2") (pintype "passive"))
      (node (ref "X1") (pin "3") (pinfunction "3_3") (pintype "passive"))
      (node (ref "X1") (pin "4") (pinfunction "4_4") (pintype "passive"))
    )
    (net (code "39") (name "Net-(R41-Pad2)") (class "Default")
      (node (ref "R41") (pin "2") (pinfunction "2_2") (pintype "passive"))
      (node (ref "R42") (pin "1") (pinfunction "1_1") (pintype "passive"))
      (node (ref "R43") (pin "2") (pinfunction "2_2") (pintype "passive"))
    )
    (net (code "40") (name "Net-(S-RESET-S)") (class "Default")
      (node (ref "D12") (pin "A") (pinfunction "A_A") (pintype "passive"))
      (node (ref "S-RESET") (pin "T") (pinfunction "S_T") (pintype "passive"))
    )
    (net (code "41") (name "Net-(U1A-+IN)") (class "Default")
      (node (ref "C2") (pin "1") (pinfunction "1_1") (pintype "passive"))
      (node (ref "R3") (pin "2") (pinfunction "2_2") (pintype "passive"))
      (node (ref "U1") (pin "3") (pinfunction "+IN_3") (pintype "input"))
    )
    (net (code "42") (name "Net-(U1A-OUT)") (class "Default")
      (node (ref "C1") (pin "1") (pinfunction "1_1") (pintype "passive"))
      (node (ref "R1") (pin "2") (pinfunction "2_2") (pintype "passive"))
      (node (ref "R2") (pin "2") (pinfunction "2_2") (pintype "passive"))
      (node (ref "U1") (pin "1") (pinfunction "OUT_1") (pintype "output"))
      (node (ref "U2") (pin "1") (pinfunction "IN_1") (pintype "bidirectional"))
    )
    (net (code "43") (name "Net-(U1B--IN)") (class "Default")
      (node (ref "D1") (pin "A") (pinfunction "A_A") (pintype "passive"))
      (node (ref "R2") (pin "1") (pinfunction "1_1") (pintype "passive"))
      (node (ref "R4") (pin "2") (pinfunction "2_2") (pintype "passive"))
      (node (ref "U1") (pin "6") (pinfunction "-IN_6") (pintype "input"))
    )
    (net (code "44") (name "Net-(U1B-OUT)") (class "Default")
      (node (ref "D2") (pin "C") (pinfunction "C_C") (pintype "passive"))
      (node (ref "R4") (pin "1") (pinfunction "1_1") (pintype "passive"))
      (node (ref "U1") (pin "7") (pinfunction "OUT_7") (pintype "output"))
      (node (ref "U2") (pin "10") (pinfunction "IN_10") (pintype "bidirectional"))
      (node (ref "U2") (pin "4") (pinfunction "IN_4") (pintype "bidirectional"))
    )
    (net (code "45") (name "Net-(U1C-OUT)") (class "Default")
      (node (ref "R37") (pin "1") (pinfunction "1_1") (pintype "passive"))
      (node (ref "R7") (pin "2") (pinfunction "2_2") (pintype "passive"))
      (node (ref "R8") (pin "1") (pinfunction "1_1") (pintype "passive"))
      (node (ref "R9") (pin "1") (pinfunction "1_1") (pintype "passive"))
      (node (ref "U1") (pin "8") (pinfunction "OUT_8") (pintype "output"))
    )
    (net (code "46") (name "Net-(U1D--IN)") (class "Default")
      (node (ref "C4") (pin "2") (pinfunction "2_2") (pintype "passive"))
      (node (ref "R5") (pin "1") (pinfunction "1_1") (pintype "passive"))
      (node (ref "R6") (pin "1") (pinfunction "1_1") (pintype "passive"))
      (node (ref "R7") (pin "1") (pinfunction "1_1") (pintype "passive"))
      (node (ref "U1") (pin "13") (pinfunction "-IN_13") (pintype "input"))
    )
    (net (code "47") (name "Net-(U1D-OUT)") (class "Default")
      (node (ref "C4") (pin "1") (pinfunction "1_1") (pintype "passive"))
      (node (ref "D3") (pin "C") (pinfunction "C_C") (pintype "passive"))
      (node (ref "D4") (pin "A") (pinfunction "A_A") (pintype "passive"))
      (node (ref "R28") (pin "1") (pinfunction "1_1") (pintype "passive"))
      (node (ref "U1") (pin "14") (pinfunction "OUT_14") (pintype "output"))
    )
    (net (code "48") (name "Net-(U2A-OUT)") (class "Default")
      (node (ref "R29") (pin "2") (pinfunction "2_2") (pintype "passive"))
      (node (ref "U2") (pin "2") (pinfunction "OUT_2") (pintype "bidirectional"))
    )
    (net (code "49") (name "Net-(U2B-OUT)") (class "Default")
      (node (ref "R3") (pin "1") (pinfunction "1_1") (pintype "passive"))
      (node (ref "U2") (pin "3") (pinfunction "OUT_3") (pintype "bidirectional"))
    )
    (net (code "50") (name "Net-(U2D-OUT)") (class "Default")
      (node (ref "R27") (pin "2") (pinfunction "2_2") (pintype "passive"))
      (node (ref "U2") (pin "11") (pinfunction "OUT_11") (pintype "bidirectional"))
    )
    (net (code "51") (name "Net-(U3-C1(1))") (class "Default")
      (node (ref "C23") (pin "1") (pinfunction "1_1") (pintype "passive"))
      (node (ref "U3") (pin "6") (pinfunction "C1(1)_6") (pintype "input"))
    )
    (net (code "52") (name "Net-(U3-C1(2))") (class "Default")
      (node (ref "C23") (pin "2") (pinfunction "2_2") (pintype "passive"))
      (node (ref "U3") (pin "7") (pinfunction "C1(2)_7") (pintype "bidirectional"))
    )
    (net (code "53") (name "Net-(U3-R1_TO_VSS)") (class "Default")
      (node (ref "R31") (pin "2") (pinfunction "2_2") (pintype "passive"))
      (node (ref "U3") (pin "11") (pinfunction "R1_TO_VSS_11") (pintype "power_in"))
    )
    (net (code "54") (name "Net-(U3-VCO_OUT)") (class "Default")
      (node (ref "C25") (pin "1") (pinfunction "1_1") (pintype "passive"))
      (node (ref "U3") (pin "4") (pinfunction "VCO_OUT_4") (pintype "output"))
    )
    (net (code "55") (name "Net-(U3-VDD)") (class "Default")
      (node (ref "C24") (pin "+") (pinfunction "+_+") (pintype "passive"))
      (node (ref "R24") (pin "1") (pinfunction "1_1") (pintype "passive"))
      (node (ref "U3") (pin "16") (pinfunction "VDD_16") (pintype "power_in"))
    )
    (net (code "56") (name "Net-(U4A-CTRL)") (class "Default")
      (node (ref "R12") (pin "2") (pinfunction "2_2") (pintype "passive"))
      (node (ref "U4") (pin "13") (pinfunction "CTRL_13") (pintype "bidirectional"))
    )
    (net (code "57") (name "Net-(U4A-IN)") (class "Default")
      (node (ref "U4") (pin "1") (pinfunction "IN_1") (pintype "bidirectional"))
      (node (ref "U4") (pin "4") (pinfunction "IN_4") (pintype "bidirectional"))
    )
    (net (code "58") (name "Net-(U5--TR_(2))") (class "Default")
      (node (ref "U5") (pin "11") (pinfunction "-TR_(2)_11") (pintype "input"))
      (node (ref "U5") (pin "6") (pinfunction "Q1_6") (pintype "output"))
    )
    (net (code "59") (name "Net-(U5-RXCX_(2))") (class "Default")
      (node (ref "D10") (pin "C") (pinfunction "C_C") (pintype "passive"))
      (node (ref "U5") (pin "14") (pinfunction "RXCX_(2)_14") (pintype "input"))
    )
    (net (code "60") (name "Net-(U6--TR_(2))") (class "Default")
      (node (ref "U6") (pin "11") (pinfunction "-TR_(2)_11") (pintype "input"))
      (node (ref "U6") (pin "6") (pinfunction "Q1_6") (pintype "output"))
    )
    (net (code "61") (name "Net-(U6-RXCX_(2))") (class "Default")
      (node (ref "D9") (pin "C") (pinfunction "C_C") (pintype "passive"))
      (node (ref "U6") (pin "14") (pinfunction "RXCX_(2)_14") (pintype "input"))
    )
    (net (code "62") (name "Net-(U7-DIS2)") (class "Default")
      (node (ref "C15") (pin "1") (pinfunction "1_1") (pintype "passive"))
      (node (ref "R25") (pin "2") (pinfunction "2_2") (pintype "passive"))
      (node (ref "U7") (pin "12") (pinfunction "TRES2_12") (pintype "input"))
      (node (ref "U7") (pin "13") (pinfunction "DIS2_13") (pintype "input"))
    )
    (net (code "63") (name "Net-(U7-TRIG2)") (class "Default")
      (node (ref "C16") (pin "2") (pinfunction "2_2") (pintype "passive"))
      (node (ref "D7") (pin "A") (pinfunction "A_A") (pintype "passive"))
      (node (ref "R22") (pin "1") (pinfunction "1_1") (pintype "passive"))
      (node (ref "U7") (pin "8") (pinfunction "TRIG2_8") (pintype "input"))
    )
    (net (code "64") (name "Net-(U8-+IN)") (class "Default")
      (node (ref "R15") (pin "2") (pinfunction "2_2") (pintype "passive"))
      (node (ref "R17") (pin "2") (pinfunction "2_2") (pintype "passive"))
      (node (ref "U8") (pin "3") (pinfunction "+IN_3") (pintype "input"))
    )
    (net (code "65") (name "Net-(U8--IN)") (class "Default")
      (node (ref "C14") (pin "2") (pinfunction "2_2") (pintype "passive"))
      (node (ref "D5") (pin "C") (pinfunction "C_C") (pintype "passive"))
      (node (ref "D6") (pin "A") (pinfunction "A_A") (pintype "passive"))
      (node (ref "R18") (pin "2") (pinfunction "2_2") (pintype "passive"))
      (node (ref "R19") (pin "2") (pinfunction "2_2") (pintype "passive"))
      (node (ref "U8") (pin "2") (pinfunction "-IN_2") (pintype "input"))
    )
    (net (code "66") (name "Net-(U9A-+IN)") (class "Default")
      (node (ref "C9") (pin "2") (pinfunction "2_2") (pintype "passive"))
      (node (ref "R14") (pin "2") (pinfunction "2_2") (pintype "passive"))
      (node (ref "R16") (pin "1") (pinfunction "1_1") (pintype "passive"))
      (node (ref "U9") (pin "3") (pinfunction "+IN_3") (pintype "input"))
    )
    (net (code "67") (name "Net-(U9B--IN)") (class "Default")
      (node (ref "C10") (pin "2") (pinfunction "2_2") (pintype "passive"))
      (node (ref "R11") (pin "1") (pinfunction "1_1") (pintype "passive"))
      (node (ref "U9") (pin "6") (pinfunction "-IN_6") (pintype "input"))
    )
    (net (code "68") (name "Net-(U9B-OUT)") (class "Default")
      (node (ref "C10") (pin "1") (pinfunction "1_1") (pintype "passive"))
      (node (ref "R15") (pin "1") (pinfunction "1_1") (pintype "passive"))
      (node (ref "U9") (pin "7") (pinfunction "OUT_7") (pintype "output"))
    )
    (net (code "69") (name "Net-(U10-+IN)") (class "Default")
      (node (ref "R41") (pin "1") (pinfunction "1_1") (pintype "passive"))
      (node (ref "U10") (pin "3") (pinfunction "+IN_3") (pintype "input"))
    )
    (net (code "70") (name "Net-(U10-OUT)") (class "Default")
      (node (ref "C29") (pin "2") (pinfunction "2_2") (pintype "passive"))
      (node (ref "U1") (pin "10") (pinfunction "+IN_10") (pintype "input"))
      (node (ref "U10") (pin "6") (pinfunction "OUT_6") (pintype "output"))
    )
    (net (code "71") (name "Net-(U11A-A)") (class "Default")
      (node (ref "R36") (pin "2") (pinfunction "2_2") (pintype "passive"))
      (node (ref "U11") (pin "11") (pinfunction "A_11") (pintype "input"))
      (node (ref "U12") (pin "7") (pinfunction "OUT_7") (pintype "output"))
    )
    (net (code "72") (name "Net-(U11A-X0)") (class "Default")
      (node (ref "R37") (pin "2") (pinfunction "2_2") (pintype "passive"))
      (node (ref "U11") (pin "12") (pinfunction "X0_12") (pintype "bidirectional"))
    )
    (net (code "73") (name "Net-(U12B--IN)") (class "Default")
      (node (ref "C26") (pin "1") (pinfunction "1_1") (pintype "passive"))
      (node (ref "D11") (pin "A") (pinfunction "A_A") (pintype "passive"))
      (node (ref "R34") (pin "1") (pinfunction "1_1") (pintype "passive"))
      (node (ref "R35") (pin "1") (pinfunction "1_1") (pintype "passive"))
      (node (ref "U12") (pin "6") (pinfunction "-IN_6") (pintype "input"))
    )
    (net (code "74") (name "Net-(U13-VI)") (class "Default")
      (node (ref "C19") (pin "+") (pinfunction "+_+") (pintype "passive"))
      (node (ref "LSP1") (pin "MP") (pinfunction "MP_MP") (pintype "passive"))
      (node (ref "U13") (pin "1") (pinfunction "VI_1") (pintype "input"))
    )
    (net (code "75") (name "Net-(U14C-OUT)") (class "Default")
      (node (ref "R27") (pin "1") (pinfunction "1_1") (pintype "passive"))
      (node (ref "R29") (pin "1") (pinfunction "1_1") (pintype "passive"))
      (node (ref "U1") (pin "9") (pinfunction "-IN_9") (pintype "input"))
      (node (ref "U14") (pin "9") (pinfunction "OUT_9") (pintype "bidirectional"))
    )
    (net (code "76") (name "Net-(U15D-IN)") (class "Default")
      (node (ref "C14") (pin "1") (pinfunction "1_1") (pintype "passive"))
      (node (ref "R18") (pin "1") (pinfunction "1_1") (pintype "passive"))
      (node (ref "R20") (pin "2") (pinfunction "2_2") (pintype "passive"))
      (node (ref "U15") (pin "10") (pinfunction "IN_10") (pintype "bidirectional"))
      (node (ref "U8") (pin "6") (pinfunction "OUT_6") (pintype "output"))
    )
    (net (code "77") (name "Net-(U15D-OUT)") (class "Default")
      (node (ref "R11") (pin "2") (pinfunction "2_2") (pintype "passive"))
      (node (ref "U15") (pin "11") (pinfunction "OUT_11") (pintype "bidirectional"))
    )
    (net (code "78") (name "U11-2") (class "Default")
      (node (ref "C29") (pin "1") (pinfunction "1_1") (pintype "passive"))
      (node (ref "U10") (pin "2") (pinfunction "-IN_2") (pintype "input"))
      (node (ref "U11") (pin "13") (pinfunction "X1_13") (pintype "bidirectional"))
      (node (ref "U11") (pin "14") (pinfunction "X_14") (pintype "bidirectional"))
    )
    (net (code "79") (name "V+") (class "Default")
      (node (ref "LED1") (pin "A") (pinfunction "A_A") (pintype "passive"))
      (node (ref "Q5") (pin "1") (pinfunction "E_1") (pintype "passive"))
    )
    (net (code "80") (name "VCC") (class "Default")
      (node (ref "D7") (pin "C") (pinfunction "C_C") (pintype "passive"))
      (node (ref "R-DELAY") (pin "1") (pinfunction "A_1") (pintype "passive"))
      (node (ref "R-GND") (pin "1") (pinfunction "A_1") (pintype "passive"))
      (node (ref "R-TXBOOST") (pin "2") (pinfunction "S_2") (pintype "passive"))
      (node (ref "R22") (pin "2") (pinfunction "2_2") (pintype "passive"))
      (node (ref "R23") (pin "2") (pinfunction "2_2") (pintype "passive"))
      (node (ref "R26") (pin "2") (pinfunction "2_2") (pintype "passive"))
      (node (ref "U5") (pin "16") (pinfunction "VDD_16") (pintype "input"))
      (node (ref "U6") (pin "16") (pinfunction "VDD_16") (pintype "input"))
      (node (ref "U7") (pin "10") (pinfunction "RESET2_10") (pintype "input"))
      (node (ref "U7") (pin "14") (pinfunction "VCC_14") (pintype "power_in"))
      (node (ref "U7") (pin "4") (pinfunction "RESET1_4") (pintype "input"))
    )
    (net (code "81") (name "VU-METER") (class "Default")
      (node (ref "D15") (pin "C") (pinfunction "C_C") (pintype "passive"))
    )
    (net (code "82") (name "unconnected-(Q2-B-Pad2)") (class "Default")
      (node (ref "Q2") (pin "2") (pinfunction "B_2") (pintype "passive"))
    )
    (net (code "83") (name "unconnected-(Q2-E-Pad1)") (class "Default")
      (node (ref "Q2") (pin "1") (pinfunction "E_1") (pintype "passive"))
    )
    (net (code "84") (name "unconnected-(Q3'-E-Pad1)") (class "Default")
      (node (ref "Q3'") (pin "1") (pinfunction "E_1") (pintype "passive"))
    )
    (net (code "85") (name "unconnected-(R-FREQ-A-Pad1)") (class "Default")
      (node (ref "R-FREQ") (pin "1") (pinfunction "A_1") (pintype "passive"))
    )
    (net (code "86") (name "unconnected-(R-FREQ-TUNE-E-Pad3)") (class "Default")
      (node (ref "R-FREQ-TUNE") (pin "3") (pinfunction "E_3") (pintype "passive"))
    )
    (net (code "87") (name "unconnected-(R-TXBOOST-A-Pad1)") (class "Default")
      (node (ref "R-TXBOOST") (pin "1") (pinfunction "A_1") (pintype "passive"))
    )
    (net (code "88") (name "unconnected-(U3-COMP_IN-Pad3)") (class "Default")
      (node (ref "U3") (pin "3") (pinfunction "COMP_IN_3") (pintype "input"))
    )
    (net (code "89") (name "unconnected-(U3-DEMODULATION_OUT-Pad10)") (class "Default")
      (node (ref "U3") (pin "10") (pinfunction "DEMODULATION_OUT_10") (pintype "output"))
    )
    (net (code "90") (name "unconnected-(U3-PHASE_COMP_II_OUT-Pad13)") (class "Default")
      (node (ref "U3") (pin "13") (pinfunction "PHASE_COMP_II_OUT_13") (pintype "output"))
    )
    (net (code "91") (name "unconnected-(U3-PHASE_COMP_I_OUT-Pad2)") (class "Default")
      (node (ref "U3") (pin "2") (pinfunction "PHASE_COMP_I_OUT_2") (pintype "output"))
    )
    (net (code "92") (name "unconnected-(U3-PHASE_PULSES-Pad1)") (class "Default")
      (node (ref "U3") (pin "1") (pinfunction "PHASE_PULSES_1") (pintype "input"))
    )
    (net (code "93") (name "unconnected-(U3-SIGNAL_IN-Pad14)") (class "Default")
      (node (ref "U3") (pin "14") (pinfunction "SIGNAL_IN_14") (pintype "input"))
    )
    (net (code "94") (name "unconnected-(U3-ZENER-Pad15)") (class "Default")
      (node (ref "U3") (pin "15") (pinfunction "ZENER_15") (pintype "bidirectional"))
    )
    (net (code "95") (name "unconnected-(U4A-OUT-Pad2)") (class "Default")
      (node (ref "U4") (pin "2") (pinfunction "OUT_2") (pintype "bidirectional"))
    )
    (net (code "96") (name "unconnected-(U4B-OUT-Pad3)") (class "Default")
      (node (ref "U4") (pin "3") (pinfunction "OUT_3") (pintype "bidirectional"))
    )
    (net (code "97") (name "unconnected-(U5-RESET_(1)-Pad3)") (class "Default")
      (node (ref "U5") (pin "3") (pinfunction "RESET_(1)_3") (pintype "input"))
    )
    (net (code "98") (name "unconnected-(U5-RESET_(2)-Pad13)") (class "Default")
      (node (ref "U5") (pin "13") (pinfunction "RESET_(2)_13") (pintype "input"))
    )
    (net (code "99") (name "unconnected-(U5-~{Q1}-Pad7)") (class "Default")
      (node (ref "U5") (pin "7") (pinfunction "~{Q1}_7") (pintype "output"))
    )
    (net (code "100") (name "unconnected-(U5-~{Q2}-Pad9)") (class "Default")
      (node (ref "U5") (pin "9") (pinfunction "~{Q2}_9") (pintype "output"))
    )
    (net (code "101") (name "unconnected-(U6-RESET_(1)-Pad3)") (class "Default")
      (node (ref "U6") (pin "3") (pinfunction "RESET_(1)_3") (pintype "input"))
    )
    (net (code "102") (name "unconnected-(U6-~{Q1}-Pad7)") (class "Default")
      (node (ref "U6") (pin "7") (pinfunction "~{Q1}_7") (pintype "output"))
    )
    (net (code "103") (name "unconnected-(U6-~{Q2}-Pad9)") (class "Default")
      (node (ref "U6") (pin "9") (pinfunction "~{Q2}_9") (pintype "output"))
    )
    (net (code "104") (name "unconnected-(U7-CONT1-Pad3)") (class "Default")
      (node (ref "U7") (pin "3") (pinfunction "CONT1_3") (pintype "input"))
    )
    (net (code "105") (name "unconnected-(U7-CONT2-Pad11)") (class "Default")
      (node (ref "U7") (pin "11") (pinfunction "CONT2_11") (pintype "input"))
    )
    (net (code "106") (name "unconnected-(U8-ON1-Pad1)") (class "Default")
      (node (ref "U8") (pin "1") (pinfunction "ON1_1") (pintype "passive"))
    )
    (net (code "107") (name "unconnected-(U8-ON2-Pad5)") (class "Default")
      (node (ref "U8") (pin "5") (pinfunction "ON2_5") (pintype "passive"))
    )
    (net (code "108") (name "unconnected-(U8-OPT-Pad8)") (class "Default")
      (node (ref "U8") (pin "8") (pinfunction "OPT_8") (pintype "passive"))
    )
    (net (code "109") (name "unconnected-(U10-ON1-Pad1)") (class "Default")
      (node (ref "U10") (pin "1") (pinfunction "ON1_1") (pintype "passive"))
    )
    (net (code "110") (name "unconnected-(U10-ON2-Pad5)") (class "Default")
      (node (ref "U10") (pin "5") (pinfunction "ON2_5") (pintype "passive"))
    )
    (net (code "111") (name "unconnected-(U10-OPT-Pad8)") (class "Default")
      (node (ref "U10") (pin "8") (pinfunction "OPT_8") (pintype "passive"))
    )
    (net (code "112") (name "unconnected-(U11A-B-Pad10)") (class "Default")
      (node (ref "U11") (pin "10") (pinfunction "B_10") (pintype "input"))
    )
    (net (code "113") (name "unconnected-(U11A-C-Pad9)") (class "Default")
      (node (ref "U11") (pin "9") (pinfunction "C_9") (pintype "input"))
    )
    (net (code "114") (name "unconnected-(U11A-Y-Pad15)") (class "Default")
      (node (ref "U11") (pin "15") (pinfunction "Y_15") (pintype "bidirectional"))
    )
    (net (code "115") (name "unconnected-(U11A-Y0-Pad2)") (class "Default")
      (node (ref "U11") (pin "2") (pinfunction "Y0_2") (pintype "bidirectional"))
    )
    (net (code "116") (name "unconnected-(U11A-Y1-Pad1)") (class "Default")
      (node (ref "U11") (pin "1") (pinfunction "Y1_1") (pintype "bidirectional"))
    )
    (net (code "117") (name "unconnected-(U11A-Z-Pad4)") (class "Default")
      (node (ref "U11") (pin "4") (pinfunction "Z_4") (pintype "bidirectional"))
    )
    (net (code "118") (name "unconnected-(U11A-Z0-Pad5)") (class "Default")
      (node (ref "U11") (pin "5") (pinfunction "Z0_5") (pintype "bidirectional"))
    )
    (net (code "119") (name "unconnected-(U11A-Z1-Pad3)") (class "Default")
      (node (ref "U11") (pin "3") (pinfunction "Z1_3") (pintype "bidirectional"))
    )
    (net (code "120") (name "unconnected-(U14C-CTRL-Pad6)") (class "Default")
      (node (ref "U14") (pin "6") (pinfunction "CTRL_6") (pintype "bidirectional"))
    )
    (net (code "121") (name "unconnected-(U15D-CTRL-Pad12)") (class "Default")
      (node (ref "U15") (pin "12") (pinfunction "CTRL_12") (pintype "bidirectional"))
    )
  )
)
